# SH4_-_POWER.net
KiCad netlist of a schematic drawn in Altium Designer
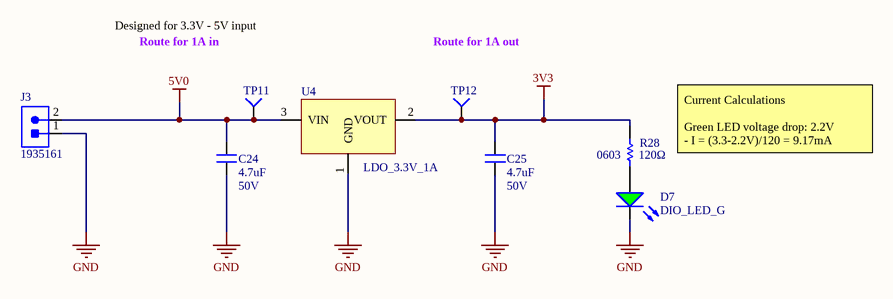
[diagram p0: SH4 - POWER.SchDoc]

(export (version "E")
  (design (tool "Eeschema 10.0.6"))
  (components
    (comp (ref "C24")
      (value "CAP_4.7uF_50V_1206")
      (footprint "CAP1206")
      (description "CAP CER 4.7UF 50V X7R 1206")
      (fields (field (name "CAPACITANCE") "4.7uF") (field (name "VOLTAGE") "50V"))
      (libsource (lib "UWRT_Schematic_Library_2020") (part "CAP_4.7uF_50V_1206"))
    )
    (comp (ref "C25")
      (value "CAP_4.7uF_50V_1206")
      (footprint "CAP1206")
      (description "CAP CER 4.7UF 50V X7R 1206")
      (fields (field (name "CAPACITANCE") "4.7uF") (field (name "VOLTAGE") "50V"))
      (libsource (lib "UWRT_Schematic_Library_2020") (part "CAP_4.7uF_50V_1206"))
    )
    (comp (ref "D7")
      (value "DIO_LED_G")
      (footprint "LED_0805_GREEN")
      (description "LED GREEN DIFFUSED 0805 SMD")
      (libsource (lib "UWRT_Schematic_Library_2020") (part "DIO_LED_G"))
    )
    (comp (ref "J3")
      (value "CON_2M_TERM")
      (footprint "1935161")
      (description "TERM BLK 2POS SIDE ENTRY 5MM")
      (fields (field (name "VOLTAGE") "300V") (field (name "MANUFACTURER PART NUMBER 1") "1935161"))
      (libsource (lib "UWRT_Schematic_Library_2020") (part "CON_2M_TERM"))
    )
    (comp (ref "R28")
      (value "120Ω")
      (footprint "RESC0603")
      (description "RES 120 OHM 5% 1/10W 0603")
      (fields (field (name "PACKAGE/FOOTPRINT") "0603") (field (name "Comment") "RES_120Ω_0603"))
      (libsource (lib "UWRT_Schematic_Library_2020") (part "RES_120Ω_0603_5%"))
    )
    (comp (ref "TP11")
      (value "TESTPOINT_SMD_LOOP")
      (footprint "S1751-46R")
      (description "PC TEST POINT SMD")
      (libsource (lib "UWRT_Schematic_Library_2020") (part "TESTPOINT_SMD_LOOP"))
    )
    (comp (ref "TP12")
      (value "TESTPOINT_SMD_LOOP")
      (footprint "S1751-46R")
      (description "PC TEST POINT SMD")
      (libsource (lib "UWRT_Schematic_Library_2020") (part "TESTPOINT_SMD_LOOP"))
    )
    (comp (ref "U4")
      (value "LDO_3.3V_1A")
      (description "IC REG LINEAR 3.3V 1A SOT223")
      (libsource (lib "UWRT_Schematic_Library_2020") (part "LDO_3.3V_1A"))
    )
  )
  (nets
    (net (code "1") (name "3V3") (class "Default")
      (node (ref "C25") (pin "2") (pinfunction "2_2") (pintype "passive"))
      (node (ref "R28") (pin "2") (pinfunction "2_2") (pintype "passive"))
      (node (ref "TP12") (pin "1") (pinfunction "=value_1") (pintype "passive"))
      (node (ref "U4") (pin "2") (pinfunction "VOUT_2") (pintype "passive"))
    )
    (net (code "2") (name "5V0") (class "Default")
      (node (ref "C24") (pin "2") (pinfunction "2_2") (pintype "passive"))
      (node (ref "J3") (pin "2") (pinfunction "2_2") (pintype "passive"))
      (node (ref "TP11") (pin "1") (pinfunction "=value_1") (pintype "passive"))
      (node (ref "U4") (pin "3") (pinfunction "VIN_3") (pintype "passive"))
    )
    (net (code "3") (name "GND") (class "Default")
      (node (ref "C24") (pin "1") (pinfunction "1_1") (pintype "passive"))
      (node (ref "C25") (pin "1") (pinfunction "1_1") (pintype "passive"))
      (node (ref "D7") (pin "2") (pinfunction "K_2") (pintype "passive"))
      (node (ref "J3") (pin "1") (pinfunction "1_1") (pintype "passive"))
      (node (ref "U4") (pin "1") (pinfunction "GND_1") (pintype "passive"))
    )
    (net (code "4") (name "Net-(D7-A)") (class "Default")
      (node (ref "D7") (pin "1") (pinfunction "A_1") (pintype "passive"))
      (node (ref "R28") (pin "1") (pinfunction "1_1") (pintype "passive"))
    )
  )
)
